# Encoder.net
KiCad netlist of a schematic drawn in Altium Designer
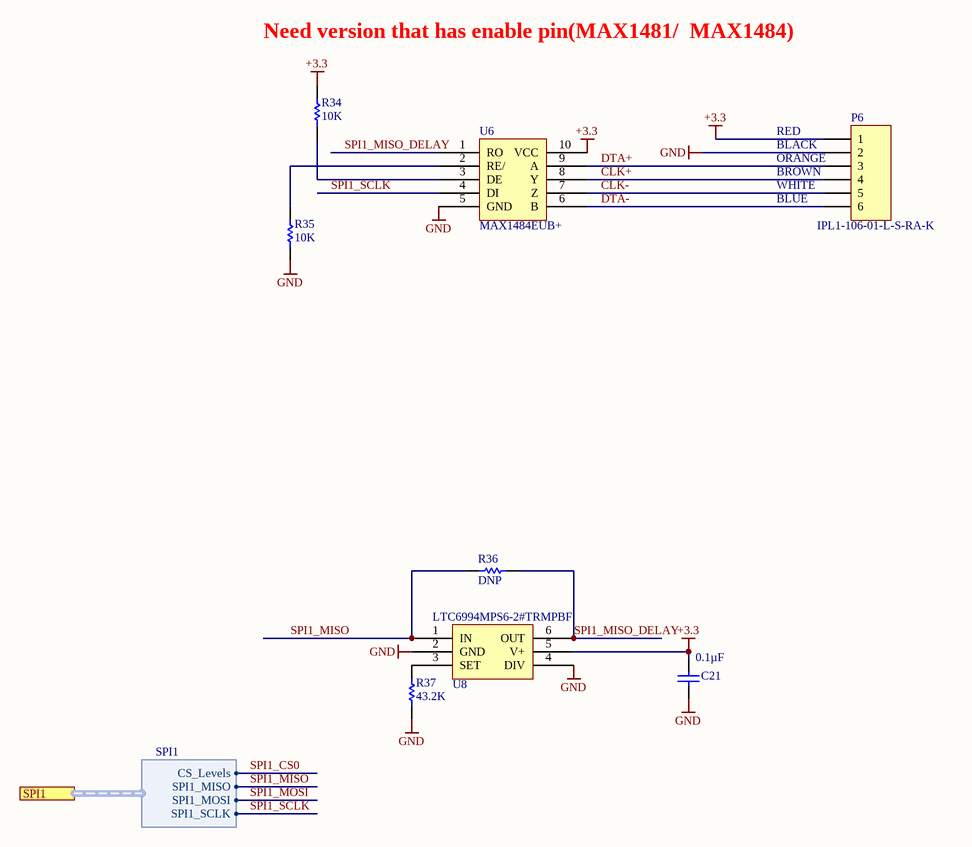
[diagram p0: Encoder.SchDoc]

(export (version "E")
  (design (tool "Eeschema 10.0.6"))
  (components
    (comp (ref "C21")
      (value "CAP CER 0.1UF 25V X7R 0805")
      (footprint "CAPC0805(2012)145_N")
      (fields
        (field (name "MANUFACTURER") "Murata Electronics North America")
        (field (name "MANUFACTURER PART NUMBER") "GRM21BR71E104KA01L")
        (field (name "CAPACITANCE") "0.1µF")
        (field (name "TOLERANCE") "±10%")
      )
      (libsource (lib "Altium Content Vault") (part "CMP-1036-04795-1"))
    )
    (comp (ref "P6")
      (value "IPL1-106-01-L-S-RA-K")
      (footprint "IPL1-106-01-L-S-RA-K")
      (description "Header, 6-Pin")
      (fields (field (name "MANUFACTURER") "Samtec Inc."))
      (libsource (lib "Miscellaneous Connectors") (part "Header 6"))
    )
    (comp (ref "R34")
      (value "10K")
      (footprint "RESC0805(2012)_L")
      (description "RES SMD 10K OHM 1% 1/8W 0805")
      (fields
        (field (name "MANUFACTURER") "Vishay Dale")
        (field (name "MANUFACTURER PART NUMBER") "CRCW080510K0FKEA")
      )
      (libsource (lib "Altium Content Vault") (part "CMP-1013-00215-1"))
    )
    (comp (ref "R35")
      (value "10K")
      (footprint "RESC0805(2012)_L")
      (description "RES SMD 10K OHM 1% 1/8W 0805")
      (fields
        (field (name "MANUFACTURER") "Vishay Dale")
        (field (name "MANUFACTURER PART NUMBER") "CRCW080510K0FKEA")
      )
      (libsource (lib "Altium Content Vault") (part "CMP-1013-00215-1"))
    )
    (comp (ref "R36")
      (value "DNP")
      (footprint "RESC0805(2012)_L")
      (description "RES SMD 0 OHM 5% 1/8W 0805")
      (libsource (lib "Altium Content Vault") (part "CMP-1013-00215-1"))
    )
    (comp (ref "R37")
      (value "43.2K")
      (footprint "RESC0805(2012)_L")
      (description "RES SMD 43.2K OHM 1% 1/8W 0805")
      (fields
        (field (name "MANUFACTURER") "Vishay Dale")
        (field (name "MANUFACTURER PART NUMBER") "CRCW080543K2FKEA")
      )
      (libsource (lib "Altium Content Vault") (part "CMP-1013-00215-1"))
    )
    (comp (ref "U6")
      (value "MAX1484EUB+")
      (footprint "MAX1484EUB+")
      (description "IC TXRX RS485/RS422 10-UMAX")
      (fields (field (name "MANUFACTURER") "Maxim Integrated") (field (name "BASE PART NUMBER") "MAX1484"))
      (libsource (lib "ZLS_Schematic_lib") (part "MAX1484EUB+"))
    )
    (comp (ref "U8")
      (value "LTC6994MPS6-2#TRMPBF")
      (footprint "LTC6994MPS6-2#TRMPBF")
      (fields
        (field (name "MANUFACTURER") "Linear Technology/Analog Devices")
        (field (name "MANUFACTURER PART NUMBER") "LTC6994CS6-2#TRMPBF")
        (field (name "BASE PART NUMBER") "LTC6994")
      )
      (libsource (lib "ZLS_Schematic_lib") (part "LTC6994MPS6-2#TRMPBF"))
    )
  )
  (nets
    (net (code "2") (name "+3.3") (class "Default")
      (node (ref "C21") (pin "1") (pinfunction "1_1") (pintype "passive"))
      (node (ref "P6") (pin "1") (pinfunction "1_1") (pintype "passive"))
      (node (ref "R34") (pin "2") (pinfunction "2_2") (pintype "passive"))
      (node (ref "U6") (pin "10") (pinfunction "VCC_10") (pintype "passive"))
      (node (ref "U8") (pin "5") (pinfunction "V+_5") (pintype "passive"))
    )
    (net (code "3") (name "/CLK+") (class "Default")
      (node (ref "P6") (pin "4") (pinfunction "4_4") (pintype "passive"))
      (node (ref "U6") (pin "8") (pinfunction "Y_8") (pintype "passive"))
    )
    (net (code "4") (name "/CLK-") (class "Default")
      (node (ref "P6") (pin "5") (pinfunction "5_5") (pintype "passive"))
      (node (ref "U6") (pin "7") (pinfunction "Z_7") (pintype "passive"))
    )
    (net (code "5") (name "/DTA+") (class "Default")
      (node (ref "P6") (pin "3") (pinfunction "3_3") (pintype "passive"))
      (node (ref "U6") (pin "9") (pinfunction "A_9") (pintype "passive"))
    )
    (net (code "6") (name "/DTA-") (class "Default")
      (node (ref "P6") (pin "6") (pinfunction "6_6") (pintype "passive"))
      (node (ref "U6") (pin "6") (pinfunction "B_6") (pintype "passive"))
    )
    (net (code "8") (name "/SPI1_MISO") (class "Default")
      (node (ref "R36") (pin "1") (pinfunction "1_1") (pintype "passive"))
      (node (ref "U8") (pin "1") (pinfunction "IN_1") (pintype "passive"))
    )
    (net (code "9") (name "/SPI1_MISO_DELAY") (class "Default")
      (node (ref "R36") (pin "2") (pinfunction "2_2") (pintype "passive"))
      (node (ref "U6") (pin "1") (pinfunction "RO_1") (pintype "passive"))
      (node (ref "U8") (pin "6") (pinfunction "OUT_6") (pintype "passive"))
    )
    (net (code "11") (name "/SPI1_SCLK") (class "Default")
      (node (ref "U6") (pin "4") (pinfunction "DI_4") (pintype "passive"))
    )
    (net (code "13") (name "GND") (class "Default")
      (node (ref "C21") (pin "2") (pinfunction "2_2") (pintype "passive"))
      (node (ref "P6") (pin "2") (pinfunction "2_2") (pintype "passive"))
      (node (ref "R35") (pin "1") (pinfunction "1_1") (pintype "passive"))
      (node (ref "R37") (pin "2") (pinfunction "2_2") (pintype "passive"))
      (node (ref "U6") (pin "5") (pinfunction "GND_5") (pintype "passive"))
      (node (ref "U8") (pin "2") (pinfunction "GND_2") (pintype "passive"))
      (node (ref "U8") (pin "4") (pinfunction "DIV_4") (pintype "passive"))
    )
    (net (code "14") (name "Net-(U6-DE)") (class "Default")
      (node (ref "R34") (pin "1") (pinfunction "1_1") (pintype "passive"))
      (node (ref "U6") (pin "3") (pinfunction "DE_3") (pintype "passive"))
    )
    (net (code "15") (name "Net-(U6-RE{slash})") (class "Default")
      (node (ref "R35") (pin "2") (pinfunction "2_2") (pintype "passive"))
      (node (ref "U6") (pin "2") (pinfunction "RE/_2") (pintype "passive"))
    )
    (net (code "16") (name "Net-(U8-SET)") (class "Default")
      (node (ref "R37") (pin "1") (pinfunction "1_1") (pintype "passive"))
      (node (ref "U8") (pin "3") (pinfunction "SET_3") (pintype "passive"))
    )
  )
)
